# servo-pcb.net
KiCad netlist of a schematic drawn in EAGLE
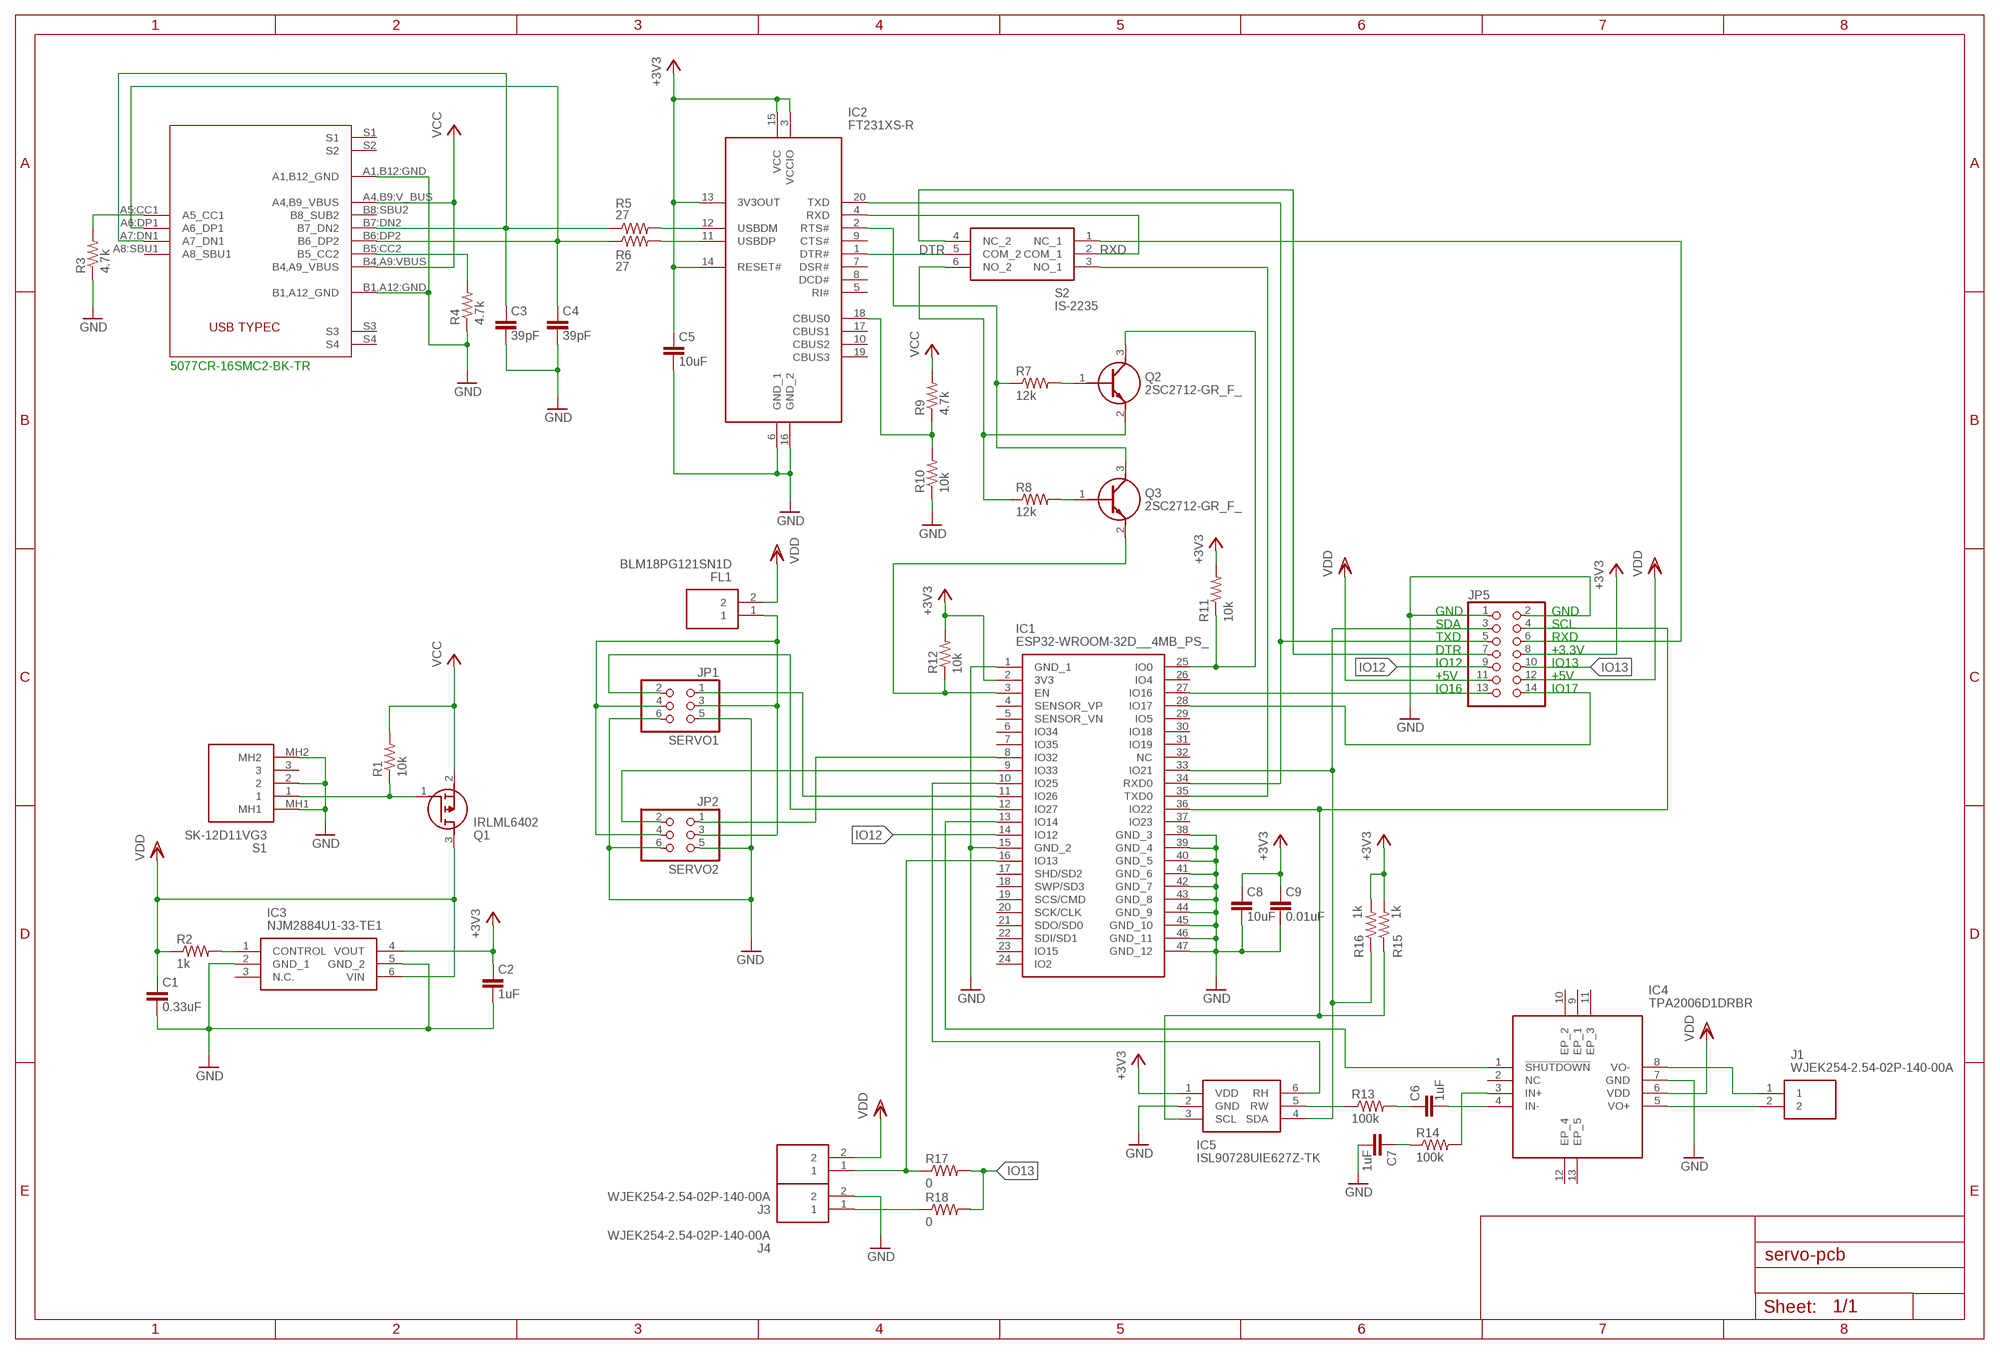
[diagram p0: schematic, sheet 1]

(export (version "E")
  (design (tool "Eeschema 10.0.6"))
  (components
    (comp (ref "C1")
      (value "0.33uF")
      (footprint "eagle-import:C0603")
      (libsource (lib "eagle-import") (part "C-EUC0603"))
    )
    (comp (ref "C2")
      (value "1uF")
      (footprint "eagle-import:C0603")
      (libsource (lib "eagle-import") (part "C-EUC0603"))
    )
    (comp (ref "C3")
      (value "39pF")
      (footprint "eagle-import:C0603")
      (libsource (lib "eagle-import") (part "C-EUC0603"))
    )
    (comp (ref "C4")
      (value "39pF")
      (footprint "eagle-import:C0603")
      (libsource (lib "eagle-import") (part "C-EUC0603"))
    )
    (comp (ref "C5")
      (value "10uF")
      (footprint "eagle-import:C0805")
      (libsource (lib "eagle-import") (part "C-EUC0805"))
    )
    (comp (ref "C6")
      (value "1uF")
      (footprint "eagle-import:C0603")
      (libsource (lib "eagle-import") (part "C-EUC0603"))
    )
    (comp (ref "C7")
      (value "1uF")
      (footprint "eagle-import:C0603")
      (libsource (lib "eagle-import") (part "C-EUC0603"))
    )
    (comp (ref "C8")
      (value "10uF")
      (footprint "eagle-import:C0805")
      (libsource (lib "eagle-import") (part "C-EUC0805"))
    )
    (comp (ref "C9")
      (value "0.01uF")
      (footprint "eagle-import:C0603")
      (libsource (lib "eagle-import") (part "C-EUC0603"))
    )
    (comp (ref "FL1")
      (value "BLM18PG121SN1D")
      (footprint "eagle-import:BLM18AG102BH1D")
      (fields (field (name "MOUSER_PART_NUMBER") "81-BLM18PG121SN1D"))
      (libsource (lib "eagle-import") (part "BLM18PG121SN1D"))
    )
    (comp (ref "IC1")
      (value "ESP32-WROOM-32D__4MB_PS_")
      (footprint "eagle-import:ESP32WROOM32D4MBPS")
      (fields
        (field (name "MANUFACTURER_PART_NUMBER") "ESP32-WROOM-32D (4MB PS)")
        (field (name "MOUSER_PART_NUMBER") "356-ESPWROOM3200PS3")
      )
      (libsource (lib "eagle-import") (part "ESP32-WROOM-32D__4MB_PS_"))
    )
    (comp (ref "IC2")
      (value "FT231XS-R")
      (footprint "eagle-import:SOP64P599X175-20N")
      (fields (field (name "MOUSER_PART_NUMBER") "895-FT231XS-R"))
      (libsource (lib "eagle-import") (part "FT231XS-R"))
    )
    (comp (ref "IC3")
      (value "NJM2884U1-33-TE1")
      (footprint "eagle-import:SOT-89-5-1")
      (fields (field (name "MOUSER_PART_NUMBER") "513-NJM2884U1-33-TE1"))
      (libsource (lib "eagle-import") (part "NJM2884U1-33-TE1"))
    )
    (comp (ref "IC4")
      (value "TPA2006D1DRBR")
      (footprint "eagle-import:TPA2006D1DRBR")
      (fields (field (name "MOUSER_PART_NUMBER") "595-TPA2006D1DRBR"))
      (libsource (lib "eagle-import") (part "TPA2006D1DRBR"))
    )
    (comp (ref "IC5")
      (value "ISL90728UIE627Z-TK")
      (footprint "eagle-import:SOT65P210X110-6N")
      (fields (field (name "MOUSER_PART_NUMBER") "968-ISL90728UIE627ZT"))
      (libsource (lib "eagle-import") (part "ISL90728UIE627Z-TK"))
    )
    (comp (ref "J1")
      (value "WJEK254-2.54-02P-140-00A")
      (footprint "eagle-import:WJEK25425402P14000A")
      (libsource (lib "eagle-import") (part "WJEK254-2.54-02P-140-00A"))
    )
    (comp (ref "J3")
      (value "WJEK254-2.54-02P-140-00A")
      (footprint "eagle-import:WJEK25425402P14000A")
      (libsource (lib "eagle-import") (part "WJEK254-2.54-02P-140-00A"))
    )
    (comp (ref "J4")
      (value "WJEK254-2.54-02P-140-00A")
      (footprint "eagle-import:WJEK25425402P14000A")
      (libsource (lib "eagle-import") (part "WJEK254-2.54-02P-140-00A"))
    )
    (comp (ref "JP1")
      (value "SERVO1")
      (footprint "eagle-import:2X03_90")
      (libsource (lib "eagle-import") (part "PINHD-2X3/90"))
    )
    (comp (ref "JP2")
      (value "SERVO2")
      (footprint "eagle-import:2X03_90")
      (libsource (lib "eagle-import") (part "PINHD-2X3/90"))
    )
    (comp (ref "JP5")
      (value "PINHD-2X7")
      (footprint "eagle-import:2X07")
      (libsource (lib "eagle-import") (part "PINHD-2X7"))
    )
    (comp (ref "Q1")
      (value "IRLML6402")
      (footprint "eagle-import:SOT95P237X112-3N")
      (libsource (lib "eagle-import") (part "IRLML6402"))
    )
    (comp (ref "Q2")
      (value "2SC2712-GR_F_")
      (footprint "eagle-import:SSM3K7002CFULF")
      (fields (field (name "MANUFACTURER_PART_NUMBER") "2SC2712-GR(F)"))
      (libsource (lib "eagle-import") (part "2SC2712-GR_F_"))
    )
    (comp (ref "Q3")
      (value "2SC2712-GR_F_")
      (footprint "eagle-import:SSM3K7002CFULF")
      (fields (field (name "MANUFACTURER_PART_NUMBER") "2SC2712-GR(F)"))
      (libsource (lib "eagle-import") (part "2SC2712-GR_F_"))
    )
    (comp (ref "R1")
      (value "10k")
      (footprint "eagle-import:R0603")
      (libsource (lib "eagle-import") (part "R-US_R0603"))
    )
    (comp (ref "R2")
      (value "1k")
      (footprint "eagle-import:R0603")
      (libsource (lib "eagle-import") (part "R-US_R0603"))
    )
    (comp (ref "R3")
      (value "4.7k")
      (footprint "eagle-import:R0603")
      (libsource (lib "eagle-import") (part "R-US_R0603"))
    )
    (comp (ref "R4")
      (value "4.7k")
      (footprint "eagle-import:R0603")
      (libsource (lib "eagle-import") (part "R-US_R0603"))
    )
    (comp (ref "R5")
      (value "27")
      (footprint "eagle-import:R0603")
      (libsource (lib "eagle-import") (part "R-US_R0603"))
    )
    (comp (ref "R6")
      (value "27")
      (footprint "eagle-import:R0603")
      (libsource (lib "eagle-import") (part "R-US_R0603"))
    )
    (comp (ref "R7")
      (value "12k")
      (footprint "eagle-import:R0603")
      (libsource (lib "eagle-import") (part "R-US_R0603"))
    )
    (comp (ref "R8")
      (value "12k")
      (footprint "eagle-import:R0603")
      (libsource (lib "eagle-import") (part "R-US_R0603"))
    )
    (comp (ref "R9")
      (value "4.7k")
      (footprint "eagle-import:R0603")
      (libsource (lib "eagle-import") (part "R-US_R0603"))
    )
    (comp (ref "R10")
      (value "10k")
      (footprint "eagle-import:R0603")
      (libsource (lib "eagle-import") (part "R-US_R0603"))
    )
    (comp (ref "R11")
      (value "10k")
      (footprint "eagle-import:R0603")
      (libsource (lib "eagle-import") (part "R-US_R0603"))
    )
    (comp (ref "R12")
      (value "10k")
      (footprint "eagle-import:R0603")
      (libsource (lib "eagle-import") (part "R-US_R0603"))
    )
    (comp (ref "R13")
      (value "100k")
      (footprint "eagle-import:R0603")
      (libsource (lib "eagle-import") (part "R-US_R0603"))
    )
    (comp (ref "R14")
      (value "100k")
      (footprint "eagle-import:R0603")
      (libsource (lib "eagle-import") (part "R-US_R0603"))
    )
    (comp (ref "R15")
      (value "1k")
      (footprint "eagle-import:R0603")
      (libsource (lib "eagle-import") (part "R-US_R0603"))
    )
    (comp (ref "R16")
      (value "1k")
      (footprint "eagle-import:R0603")
      (libsource (lib "eagle-import") (part "R-US_R0603"))
    )
    (comp (ref "R17")
      (value "0")
      (footprint "eagle-import:R0603")
      (libsource (lib "eagle-import") (part "R-US_R0603"))
    )
    (comp (ref "R18")
      (value "0")
      (footprint "eagle-import:R0603")
      (libsource (lib "eagle-import") (part "R-US_R0603"))
    )
    (comp (ref "S1")
      (value "SK-12D11VG3")
      (footprint "eagle-import:SK12D11VG3")
      (libsource (lib "eagle-import") (part "SK-12D11VG3"))
    )
    (comp (ref "S2")
      (value "IS-2235")
      (footprint "eagle-import:IS2235")
      (libsource (lib "eagle-import") (part "IS-2235"))
    )
    (comp (ref "U$1")
      (value "5077CR-16-SMC2-BK-TR")
      (footprint "eagle-import:5077CR-16SMC2-BK-TR")
      (libsource (lib "eagle-import") (part "5077CR-16-SMC2-BK-TR"))
    )
  )
  (nets
    (net (code "1") (name "+3V3") (class "Default")
      (node (ref "C2") (pin "1") (pinfunction "1_1") (pintype "passive"))
      (node (ref "C5") (pin "1") (pinfunction "1_1") (pintype "passive"))
      (node (ref "C8") (pin "1") (pinfunction "1_1") (pintype "passive"))
      (node (ref "C9") (pin "1") (pinfunction "1_1") (pintype "passive"))
      (node (ref "IC1") (pin "2") (pinfunction "3V3_2") (pintype "bidirectional"))
      (node (ref "IC2") (pin "13") (pinfunction "3V3OUT_13") (pintype "bidirectional"))
      (node (ref "IC2") (pin "14") (pinfunction "RESET#_14") (pintype "bidirectional"))
      (node (ref "IC2") (pin "15") (pinfunction "VCC_15") (pintype "bidirectional"))
      (node (ref "IC2") (pin "3") (pinfunction "VCCIO_3") (pintype "bidirectional"))
      (node (ref "IC3") (pin "4") (pinfunction "VOUT_4") (pintype "bidirectional"))
      (node (ref "IC5") (pin "1") (pinfunction "VDD_1") (pintype "bidirectional"))
      (node (ref "JP5") (pin "8") (pinfunction "8_8") (pintype "passive"))
      (node (ref "R11") (pin "2") (pinfunction "2_2") (pintype "passive"))
      (node (ref "R12") (pin "2") (pinfunction "2_2") (pintype "passive"))
      (node (ref "R15") (pin "2") (pinfunction "2_2") (pintype "passive"))
      (node (ref "R16") (pin "2") (pinfunction "2_2") (pintype "passive"))
    )
    (net (code "2") (name "/DTR") (class "Default")
      (node (ref "IC2") (pin "1") (pinfunction "DTR#_1") (pintype "bidirectional"))
      (node (ref "S2") (pin "5") (pinfunction "COM_2_5") (pintype "bidirectional"))
    )
    (net (code "3") (name "/RXD") (class "Default")
      (node (ref "IC2") (pin "4") (pinfunction "RXD_4") (pintype "bidirectional"))
      (node (ref "S2") (pin "2") (pinfunction "COM_1_2") (pintype "bidirectional"))
    )
    (net (code "4") (name "GND") (class "Default")
      (node (ref "C1") (pin "2") (pinfunction "2_2") (pintype "passive"))
      (node (ref "C2") (pin "2") (pinfunction "2_2") (pintype "passive"))
      (node (ref "C3") (pin "2") (pinfunction "2_2") (pintype "passive"))
      (node (ref "C4") (pin "2") (pinfunction "2_2") (pintype "passive"))
      (node (ref "C5") (pin "2") (pinfunction "2_2") (pintype "passive"))
      (node (ref "C7") (pin "2") (pinfunction "2_2") (pintype "passive"))
      (node (ref "C8") (pin "2") (pinfunction "2_2") (pintype "passive"))
      (node (ref "C9") (pin "2") (pinfunction "2_2") (pintype "passive"))
      (node (ref "IC1") (pin "1") (pinfunction "GND_1_1") (pintype "bidirectional"))
      (node (ref "IC1") (pin "15") (pinfunction "GND_2_15") (pintype "bidirectional"))
      (node (ref "IC1") (pin "38") (pinfunction "GND_3_38") (pintype "bidirectional"))
      (node (ref "IC1") (pin "39") (pinfunction "GND_4_39") (pintype "bidirectional"))
      (node (ref "IC1") (pin "40") (pinfunction "GND_5_40") (pintype "bidirectional"))
      (node (ref "IC1") (pin "41") (pinfunction "GND_6_41") (pintype "bidirectional"))
      (node (ref "IC1") (pin "42") (pinfunction "GND_7_42") (pintype "bidirectional"))
      (node (ref "IC1") (pin "43") (pinfunction "GND_8_43") (pintype "bidirectional"))
      (node (ref "IC1") (pin "44") (pinfunction "GND_9_44") (pintype "bidirectional"))
      (node (ref "IC1") (pin "45") (pinfunction "GND_10_45") (pintype "bidirectional"))
      (node (ref "IC1") (pin "46") (pinfunction "GND_11_46") (pintype "bidirectional"))
      (node (ref "IC1") (pin "47") (pinfunction "GND_12_47") (pintype "bidirectional"))
      (node (ref "IC2") (pin "16") (pinfunction "GND_2_16") (pintype "bidirectional"))
      (node (ref "IC2") (pin "6") (pinfunction "GND_1_6") (pintype "bidirectional"))
      (node (ref "IC3") (pin "2") (pinfunction "GND_1_2") (pintype "bidirectional"))
      (node (ref "IC3") (pin "5") (pinfunction "GND_2_5") (pintype "bidirectional"))
      (node (ref "IC4") (pin "7") (pinfunction "GND_7") (pintype "bidirectional"))
      (node (ref "IC5") (pin "2") (pinfunction "GND_2") (pintype "bidirectional"))
      (node (ref "J4") (pin "2") (pinfunction "2_2") (pintype "bidirectional"))
      (node (ref "JP1") (pin "5") (pinfunction "5_5") (pintype "passive"))
      (node (ref "JP1") (pin "6") (pinfunction "6_6") (pintype "passive"))
      (node (ref "JP2") (pin "5") (pinfunction "5_5") (pintype "passive"))
      (node (ref "JP2") (pin "6") (pinfunction "6_6") (pintype "passive"))
      (node (ref "JP5") (pin "1") (pinfunction "1_1") (pintype "passive"))
      (node (ref "JP5") (pin "2") (pinfunction "2_2") (pintype "passive"))
      (node (ref "R10") (pin "1") (pinfunction "1_1") (pintype "passive"))
      (node (ref "R3") (pin "1") (pinfunction "1_1") (pintype "passive"))
      (node (ref "R4") (pin "1") (pinfunction "1_1") (pintype "passive"))
      (node (ref "S1") (pin "2") (pinfunction "2_2") (pintype "bidirectional"))
      (node (ref "S1") (pin "MH1") (pinfunction "MH1_MH1") (pintype "bidirectional"))
      (node (ref "S1") (pin "MH2") (pinfunction "MH2_MH2") (pintype "bidirectional"))
      (node (ref "U$1") (pin "A1,B12:GND") (pinfunction "A1,B12_GND_A1,B12:GND") (pintype "bidirectional"))
      (node (ref "U$1") (pin "B1,A12:GND") (pinfunction "B1,A12_GND_B1,A12:GND") (pintype "bidirectional"))
    )
    (net (code "5") (name "IO12") (class "Default")
      (node (ref "IC1") (pin "14") (pinfunction "IO12_14") (pintype "bidirectional"))
      (node (ref "JP5") (pin "9") (pinfunction "9_9") (pintype "passive"))
    )
    (net (code "6") (name "IO13") (class "Default")
      (node (ref "JP5") (pin "10") (pinfunction "10_10") (pintype "passive"))
      (node (ref "R17") (pin "2") (pinfunction "2_2") (pintype "passive"))
      (node (ref "R18") (pin "2") (pinfunction "2_2") (pintype "passive"))
    )
    (net (code "7") (name "Net-(C6-Pad1)") (class "Default")
      (node (ref "C6") (pin "1") (pinfunction "1_1") (pintype "passive"))
      (node (ref "R13") (pin "2") (pinfunction "2_2") (pintype "passive"))
    )
    (net (code "8") (name "Net-(C7-Pad1)") (class "Default")
      (node (ref "C7") (pin "1") (pinfunction "1_1") (pintype "passive"))
      (node (ref "R14") (pin "1") (pinfunction "1_1") (pintype "passive"))
    )
    (net (code "9") (name "Net-(FL1-Pad1)") (class "Default")
      (node (ref "FL1") (pin "1") (pinfunction "1_1") (pintype "bidirectional"))
      (node (ref "JP1") (pin "3") (pinfunction "3_3") (pintype "passive"))
      (node (ref "JP1") (pin "4") (pinfunction "4_4") (pintype "passive"))
      (node (ref "JP2") (pin "3") (pinfunction "3_3") (pintype "passive"))
      (node (ref "JP2") (pin "4") (pinfunction "4_4") (pintype "passive"))
    )
    (net (code "10") (name "Net-(IC1-EN)") (class "Default")
      (node (ref "IC1") (pin "3") (pinfunction "EN_3") (pintype "bidirectional"))
      (node (ref "Q3") (pin "2") (pinfunction "E_2") (pintype "bidirectional"))
      (node (ref "R12") (pin "1") (pinfunction "1_1") (pintype "passive"))
    )
    (net (code "11") (name "Net-(IC1-IO0)") (class "Default")
      (node (ref "IC1") (pin "25") (pinfunction "IO0_25") (pintype "bidirectional"))
      (node (ref "Q2") (pin "3") (pinfunction "C_3") (pintype "bidirectional"))
      (node (ref "R11") (pin "1") (pinfunction "1_1") (pintype "passive"))
    )
    (net (code "12") (name "Net-(IC1-IO13)") (class "Default")
      (node (ref "IC1") (pin "16") (pinfunction "IO13_16") (pintype "bidirectional"))
      (node (ref "J3") (pin "1") (pinfunction "1_1") (pintype "bidirectional"))
      (node (ref "R17") (pin "1") (pinfunction "1_1") (pintype "passive"))
    )
    (net (code "13") (name "Net-(IC1-IO14)") (class "Default")
      (node (ref "IC1") (pin "13") (pinfunction "IO14_13") (pintype "bidirectional"))
      (node (ref "IC4") (pin "1") (pinfunction "~{SHUTDOWN}_1") (pintype "bidirectional"))
    )
    (net (code "14") (name "Net-(IC1-IO16)") (class "Default")
      (node (ref "IC1") (pin "27") (pinfunction "IO16_27") (pintype "bidirectional"))
      (node (ref "JP5") (pin "13") (pinfunction "13_13") (pintype "passive"))
    )
    (net (code "15") (name "Net-(IC1-IO17)") (class "Default")
      (node (ref "IC1") (pin "28") (pinfunction "IO17_28") (pintype "bidirectional"))
      (node (ref "JP5") (pin "14") (pinfunction "14_14") (pintype "passive"))
    )
    (net (code "16") (name "Net-(IC1-IO21)") (class "Default")
      (node (ref "IC1") (pin "33") (pinfunction "IO21_33") (pintype "bidirectional"))
      (node (ref "IC5") (pin "4") (pinfunction "SDA_4") (pintype "bidirectional"))
      (node (ref "JP5") (pin "3") (pinfunction "3_3") (pintype "passive"))
      (node (ref "R16") (pin "1") (pinfunction "1_1") (pintype "passive"))
    )
    (net (code "17") (name "Net-(IC1-IO22)") (class "Default")
      (node (ref "IC1") (pin "36") (pinfunction "IO22_36") (pintype "bidirectional"))
      (node (ref "IC5") (pin "3") (pinfunction "SCL_3") (pintype "bidirectional"))
      (node (ref "JP5") (pin "4") (pinfunction "4_4") (pintype "passive"))
      (node (ref "R15") (pin "1") (pinfunction "1_1") (pintype "passive"))
    )
    (net (code "18") (name "Net-(IC1-IO25)") (class "Default")
      (node (ref "IC1") (pin "10") (pinfunction "IO25_10") (pintype "bidirectional"))
      (node (ref "IC5") (pin "6") (pinfunction "RH_6") (pintype "bidirectional"))
    )
    (net (code "19") (name "Net-(IC1-IO26)") (class "Default")
      (node (ref "IC1") (pin "11") (pinfunction "IO26_11") (pintype "bidirectional"))
      (node (ref "JP1") (pin "1") (pinfunction "1_1") (pintype "passive"))
    )
    (net (code "20") (name "Net-(IC1-IO27)") (class "Default")
      (node (ref "IC1") (pin "12") (pinfunction "IO27_12") (pintype "bidirectional"))
      (node (ref "JP1") (pin "2") (pinfunction "2_2") (pintype "passive"))
    )
    (net (code "21") (name "Net-(IC1-IO32)") (class "Default")
      (node (ref "IC1") (pin "8") (pinfunction "IO32_8") (pintype "bidirectional"))
      (node (ref "JP2") (pin "1") (pinfunction "1_1") (pintype "passive"))
    )
    (net (code "22") (name "Net-(IC1-IO33)") (class "Default")
      (node (ref "IC1") (pin "9") (pinfunction "IO33_9") (pintype "bidirectional"))
      (node (ref "JP2") (pin "2") (pinfunction "2_2") (pintype "passive"))
    )
    (net (code "23") (name "Net-(IC1-RXD0)") (class "Default")
      (node (ref "IC1") (pin "34") (pinfunction "RXD0_34") (pintype "bidirectional"))
      (node (ref "IC2") (pin "20") (pinfunction "TXD_20") (pintype "bidirectional"))
      (node (ref "JP5") (pin "5") (pinfunction "5_5") (pintype "passive"))
    )
    (net (code "24") (name "Net-(IC1-TXD0)") (class "Default")
      (node (ref "IC1") (pin "35") (pinfunction "TXD0_35") (pintype "bidirectional"))
      (node (ref "S2") (pin "3") (pinfunction "NO_1_3") (pintype "bidirectional"))
    )
    (net (code "25") (name "Net-(IC2-CBUS0)") (class "Default")
      (node (ref "IC2") (pin "18") (pinfunction "CBUS0_18") (pintype "bidirectional"))
      (node (ref "R10") (pin "2") (pinfunction "2_2") (pintype "passive"))
      (node (ref "R9") (pin "1") (pinfunction "1_1") (pintype "passive"))
    )
    (net (code "26") (name "Net-(IC2-RTS#)") (class "Default")
      (node (ref "IC2") (pin "2") (pinfunction "RTS#_2") (pintype "bidirectional"))
      (node (ref "Q3") (pin "3") (pinfunction "C_3") (pintype "bidirectional"))
      (node (ref "R7") (pin "1") (pinfunction "1_1") (pintype "passive"))
    )
    (net (code "27") (name "Net-(IC2-USBDM)") (class "Default")
      (node (ref "IC2") (pin "12") (pinfunction "USBDM_12") (pintype "bidirectional"))
      (node (ref "R5") (pin "2") (pinfunction "2_2") (pintype "passive"))
    )
    (net (code "28") (name "Net-(IC2-USBDP)") (class "Default")
      (node (ref "IC2") (pin "11") (pinfunction "USBDP_11") (pintype "bidirectional"))
      (node (ref "R6") (pin "2") (pinfunction "2_2") (pintype "passive"))
    )
    (net (code "29") (name "Net-(IC3-CONTROL)") (class "Default")
      (node (ref "IC3") (pin "1") (pinfunction "CONTROL_1") (pintype "bidirectional"))
      (node (ref "R2") (pin "2") (pinfunction "2_2") (pintype "passive"))
    )
    (net (code "30") (name "Net-(IC4-IN+)") (class "Default")
      (node (ref "IC4") (pin "3") (pinfunction "IN+_3") (pintype "bidirectional"))
      (node (ref "R14") (pin "2") (pinfunction "2_2") (pintype "passive"))
    )
    (net (code "31") (name "Net-(IC4-IN-)") (class "Default")
      (node (ref "C6") (pin "2") (pinfunction "2_2") (pintype "passive"))
      (node (ref "IC4") (pin "4") (pinfunction "IN-_4") (pintype "bidirectional"))
    )
    (net (code "32") (name "Net-(IC4-VO+)") (class "Default")
      (node (ref "IC4") (pin "5") (pinfunction "VO+_5") (pintype "bidirectional"))
      (node (ref "J1") (pin "2") (pinfunction "2_2") (pintype "bidirectional"))
    )
    (net (code "33") (name "Net-(IC4-VO-)") (class "Default")
      (node (ref "IC4") (pin "8") (pinfunction "VO-_8") (pintype "bidirectional"))
      (node (ref "J1") (pin "1") (pinfunction "1_1") (pintype "bidirectional"))
    )
    (net (code "34") (name "Net-(IC5-RW)") (class "Default")
      (node (ref "IC5") (pin "5") (pinfunction "RW_5") (pintype "bidirectional"))
      (node (ref "R13") (pin "1") (pinfunction "1_1") (pintype "passive"))
    )
    (net (code "35") (name "Net-(J4-Pad1)") (class "Default")
      (node (ref "J4") (pin "1") (pinfunction "1_1") (pintype "bidirectional"))
      (node (ref "R18") (pin "1") (pinfunction "1_1") (pintype "passive"))
    )
    (net (code "36") (name "Net-(Q1-G)") (class "Default")
      (node (ref "Q1") (pin "1") (pinfunction "G_1") (pintype "bidirectional"))
      (node (ref "R1") (pin "1") (pinfunction "1_1") (pintype "passive"))
      (node (ref "S1") (pin "1") (pinfunction "1_1") (pintype "bidirectional"))
    )
    (net (code "37") (name "Net-(Q2-B)") (class "Default")
      (node (ref "Q2") (pin "1") (pinfunction "B_1") (pintype "bidirectional"))
      (node (ref "R7") (pin "2") (pinfunction "2_2") (pintype "passive"))
    )
    (net (code "38") (name "Net-(Q2-E)") (class "Default")
      (node (ref "Q2") (pin "2") (pinfunction "E_2") (pintype "bidirectional"))
      (node (ref "R8") (pin "1") (pinfunction "1_1") (pintype "passive"))
      (node (ref "S2") (pin "6") (pinfunction "NO_2_6") (pintype "bidirectional"))
    )
    (net (code "39") (name "Net-(Q3-B)") (class "Default")
      (node (ref "Q3") (pin "1") (pinfunction "B_1") (pintype "bidirectional"))
      (node (ref "R8") (pin "2") (pinfunction "2_2") (pintype "passive"))
    )
    (net (code "40") (name "Net-(S2-NC_1)") (class "Default")
      (node (ref "JP5") (pin "6") (pinfunction "6_6") (pintype "passive"))
      (node (ref "S2") (pin "1") (pinfunction "NC_1_1") (pintype "bidirectional"))
    )
    (net (code "41") (name "Net-(S2-NC_2)") (class "Default")
      (node (ref "JP5") (pin "7") (pinfunction "7_7") (pintype "passive"))
      (node (ref "S2") (pin "4") (pinfunction "NC_2_4") (pintype "bidirectional"))
    )
    (net (code "42") (name "Net-(U$1-A5_CC1)") (class "Default")
      (node (ref "R3") (pin "2") (pinfunction "2_2") (pintype "passive"))
      (node (ref "U$1") (pin "A5:CC1") (pinfunction "A5_CC1_A5:CC1") (pintype "bidirectional"))
    )
    (net (code "43") (name "Net-(U$1-A6_DP1)") (class "Default")
      (node (ref "C4") (pin "1") (pinfunction "1_1") (pintype "passive"))
      (node (ref "R6") (pin "1") (pinfunction "1_1") (pintype "passive"))
      (node (ref "U$1") (pin "A6:DP1") (pinfunction "A6_DP1_A6:DP1") (pintype "bidirectional"))
      (node (ref "U$1") (pin "B6:DP2") (pinfunction "B6_DP2_B6:DP2") (pintype "bidirectional"))
    )
    (net (code "44") (name "Net-(U$1-A7_DN1)") (class "Default")
      (node (ref "C3") (pin "1") (pinfunction "1_1") (pintype "passive"))
      (node (ref "R5") (pin "1") (pinfunction "1_1") (pintype "passive"))
      (node (ref "U$1") (pin "A7:DN1") (pinfunction "A7_DN1_A7:DN1") (pintype "bidirectional"))
      (node (ref "U$1") (pin "B7:DN2") (pinfunction "B7_DN2_B7:DN2") (pintype "bidirectional"))
    )
    (net (code "45") (name "Net-(U$1-B5_CC2)") (class "Default")
      (node (ref "R4") (pin "2") (pinfunction "2_2") (pintype "passive"))
      (node (ref "U$1") (pin "B5:CC2") (pinfunction "B5_CC2_B5:CC2") (pintype "bidirectional"))
    )
    (net (code "46") (name "VCC") (class "Default")
      (node (ref "Q1") (pin "2") (pinfunction "S_2") (pintype "bidirectional"))
      (node (ref "R1") (pin "2") (pinfunction "2_2") (pintype "passive"))
      (node (ref "R9") (pin "2") (pinfunction "2_2") (pintype "passive"))
      (node (ref "U$1") (pin "A4,B9:V_BUS") (pinfunction "A4,B9_VBUS_A4,B9:V_BUS") (pintype "bidirectional"))
      (node (ref "U$1") (pin "B4,A9:VBUS") (pinfunction "B4,A9_VBUS_B4,A9:VBUS") (pintype "bidirectional"))
    )
    (net (code "47") (name "VDD") (class "Default")
      (node (ref "C1") (pin "1") (pinfunction "1_1") (pintype "passive"))
      (node (ref "FL1") (pin "2") (pinfunction "2_2") (pintype "bidirectional"))
      (node (ref "IC3") (pin "6") (pinfunction "VIN_6") (pintype "bidirectional"))
      (node (ref "IC4") (pin "6") (pinfunction "VDD_6") (pintype "bidirectional"))
      (node (ref "J3") (pin "2") (pinfunction "2_2") (pintype "bidirectional"))
      (node (ref "JP5") (pin "11") (pinfunction "11_11") (pintype "passive"))
      (node (ref "JP5") (pin "12") (pinfunction "12_12") (pintype "passive"))
      (node (ref "Q1") (pin "3") (pinfunction "D_3") (pintype "bidirectional"))
      (node (ref "R2") (pin "1") (pinfunction "1_1") (pintype "passive"))
    )
    (net (code "48") (name "unconnected-(IC1-IO2-Pad24)") (class "Default")
      (node (ref "IC1") (pin "24") (pinfunction "IO2_24") (pintype "bidirectional"))
    )
    (net (code "49") (name "unconnected-(IC1-IO4-Pad26)") (class "Default")
      (node (ref "IC1") (pin "26") (pinfunction "IO4_26") (pintype "bidirectional"))
    )
    (net (code "50") (name "unconnected-(IC1-IO5-Pad29)") (class "Default")
      (node (ref "IC1") (pin "29") (pinfunction "IO5_29") (pintype "bidirectional"))
    )
    (net (code "51") (name "unconnected-(IC1-IO15-Pad23)") (class "Default")
      (node (ref "IC1") (pin "23") (pinfunction "IO15_23") (pintype "bidirectional"))
    )
    (net (code "52") (name "unconnected-(IC1-IO18-Pad30)") (class "Default")
      (node (ref "IC1") (pin "30") (pinfunction "IO18_30") (pintype "bidirectional"))
    )
    (net (code "53") (name "unconnected-(IC1-IO19-Pad31)") (class "Default")
      (node (ref "IC1") (pin "31") (pinfunction "IO19_31") (pintype "bidirectional"))
    )
    (net (code "54") (name "unconnected-(IC1-IO23-Pad37)") (class "Default")
      (node (ref "IC1") (pin "37") (pinfunction "IO23_37") (pintype "bidirectional"))
    )
    (net (code "55") (name "unconnected-(IC1-IO34-Pad6)") (class "Default")
      (node (ref "IC1") (pin "6") (pinfunction "IO34_6") (pintype "bidirectional"))
    )
    (net (code "56") (name "unconnected-(IC1-IO35-Pad7)") (class "Default")
      (node (ref "IC1") (pin "7") (pinfunction "IO35_7") (pintype "bidirectional"))
    )
    (net (code "57") (name "unconnected-(IC1-NC-Pad32)") (class "Default")
      (node (ref "IC1") (pin "32") (pinfunction "NC_32") (pintype "no_connect"))
    )
    (net (code "58") (name "unconnected-(IC1-SCK{slash}CLK-Pad20)") (class "Default")
      (node (ref "IC1") (pin "20") (pinfunction "SCK/CLK_20") (pintype "bidirectional"))
    )
    (net (code "59") (name "unconnected-(IC1-SCS{slash}CMD-Pad19)") (class "Default")
      (node (ref "IC1") (pin "19") (pinfunction "SCS/CMD_19") (pintype "bidirectional"))
    )
    (net (code "60") (name "unconnected-(IC1-SDI{slash}SD1-Pad22)") (class "Default")
      (node (ref "IC1") (pin "22") (pinfunction "SDI/SD1_22") (pintype "bidirectional"))
    )
    (net (code "61") (name "unconnected-(IC1-SDO{slash}SD0-Pad21)") (class "Default")
      (node (ref "IC1") (pin "21") (pinfunction "SDO/SD0_21") (pintype "bidirectional"))
    )
    (net (code "62") (name "unconnected-(IC1-SENSOR_VN-Pad5)") (class "Default")
      (node (ref "IC1") (pin "5") (pinfunction "SENSOR_VN_5") (pintype "bidirectional"))
    )
    (net (code "63") (name "unconnected-(IC1-SENSOR_VP-Pad4)") (class "Default")
      (node (ref "IC1") (pin "4") (pinfunction "SENSOR_VP_4") (pintype "bidirectional"))
    )
    (net (code "64") (name "unconnected-(IC1-SHD{slash}SD2-Pad17)") (class "Default")
      (node (ref "IC1") (pin "17") (pinfunction "SHD/SD2_17") (pintype "bidirectional"))
    )
    (net (code "65") (name "unconnected-(IC1-SWP{slash}SD3-Pad18)") (class "Default")
      (node (ref "IC1") (pin "18") (pinfunction "SWP/SD3_18") (pintype "bidirectional"))
    )
    (net (code "66") (name "unconnected-(IC2-CBUS1-Pad17)") (class "Default")
      (node (ref "IC2") (pin "17") (pinfunction "CBUS1_17") (pintype "bidirectional"))
    )
    (net (code "67") (name "unconnected-(IC2-CBUS2-Pad10)") (class "Default")
      (node (ref "IC2") (pin "10") (pinfunction "CBUS2_10") (pintype "bidirectional"))
    )
    (net (code "68") (name "unconnected-(IC2-CBUS3-Pad19)") (class "Default")
      (node (ref "IC2") (pin "19") (pinfunction "CBUS3_19") (pintype "bidirectional"))
    )
    (net (code "69") (name "unconnected-(IC2-CTS#-Pad9)") (class "Default")
      (node (ref "IC2") (pin "9") (pinfunction "CTS#_9") (pintype "bidirectional"))
    )
    (net (code "70") (name "unconnected-(IC2-DCD#-Pad8)") (class "Default")
      (node (ref "IC2") (pin "8") (pinfunction "DCD#_8") (pintype "bidirectional"))
    )
    (net (code "71") (name "unconnected-(IC2-DSR#-Pad7)") (class "Default")
      (node (ref "IC2") (pin "7") (pinfunction "DSR#_7") (pintype "bidirectional"))
    )
    (net (code "72") (name "unconnected-(IC2-RI#-Pad5)") (class "Default")
      (node (ref "IC2") (pin "5") (pinfunction "RI#_5") (pintype "bidirectional"))
    )
    (net (code "73") (name "unconnected-(IC3-N.C.-Pad3)") (class "Default")
      (node (ref "IC3") (pin "3") (pinfunction "N.C._3") (pintype "no_connect"))
    )
    (net (code "74") (name "unconnected-(IC4-EP_1-Pad9)") (class "Default")
      (node (ref "IC4") (pin "9") (pinfunction "EP_1_9") (pintype "bidirectional"))
    )
    (net (code "75") (name "unconnected-(IC4-EP_2-Pad10)") (class "Default")
      (node (ref "IC4") (pin "10") (pinfunction "EP_2_10") (pintype "bidirectional"))
    )
    (net (code "76") (name "unconnected-(IC4-EP_3-Pad11)") (class "Default")
      (node (ref "IC4") (pin "11") (pinfunction "EP_3_11") (pintype "bidirectional"))
    )
    (net (code "77") (name "unconnected-(IC4-EP_4-Pad12)") (class "Default")
      (node (ref "IC4") (pin "12") (pinfunction "EP_4_12") (pintype "bidirectional"))
    )
    (net (code "78") (name "unconnected-(IC4-EP_5-Pad13)") (class "Default")
      (node (ref "IC4") (pin "13") (pinfunction "EP_5_13") (pintype "bidirectional"))
    )
    (net (code "79") (name "unconnected-(IC4-NC-Pad2)") (class "Default")
      (node (ref "IC4") (pin "2") (pinfunction "NC_2") (pintype "no_connect"))
    )
    (net (code "80") (name "unconnected-(S1-Pad3)") (class "Default")
      (node (ref "S1") (pin "3") (pinfunction "3_3") (pintype "bidirectional"))
    )
    (net (code "81") (name "unconnected-(U$1-A8_SBU1-PadA8:SBU1)") (class "Default")
      (node (ref "U$1") (pin "A8:SBU1") (pinfunction "A8_SBU1_A8:SBU1") (pintype "bidirectional"))
    )
    (net (code "82") (name "unconnected-(U$1-B8_SUB2-PadB8:SBU2)") (class "Default")
      (node (ref "U$1") (pin "B8:SBU2") (pinfunction "B8_SUB2_B8:SBU2") (pintype "bidirectional"))
    )
    (net (code "83") (name "unconnected-(U$1-PadS1)") (class "Default")
      (node (ref "U$1") (pin "S1") (pinfunction "S1_S1") (pintype "bidirectional"))
    )
    (net (code "84") (name "unconnected-(U$1-PadS2)") (class "Default")
      (node (ref "U$1") (pin "S2") (pinfunction "S2_S2") (pintype "bidirectional"))
    )
    (net (code "85") (name "unconnected-(U$1-PadS3)") (class "Default")
      (node (ref "U$1") (pin "S3") (pinfunction "S3_S3") (pintype "bidirectional"))
    )
    (net (code "86") (name "unconnected-(U$1-PadS4)") (class "Default")
      (node (ref "U$1") (pin "S4") (pinfunction "S4_S4") (pintype "bidirectional"))
    )
  )
)
